# untitled.net
KiCad netlist of a schematic drawn in EAGLE
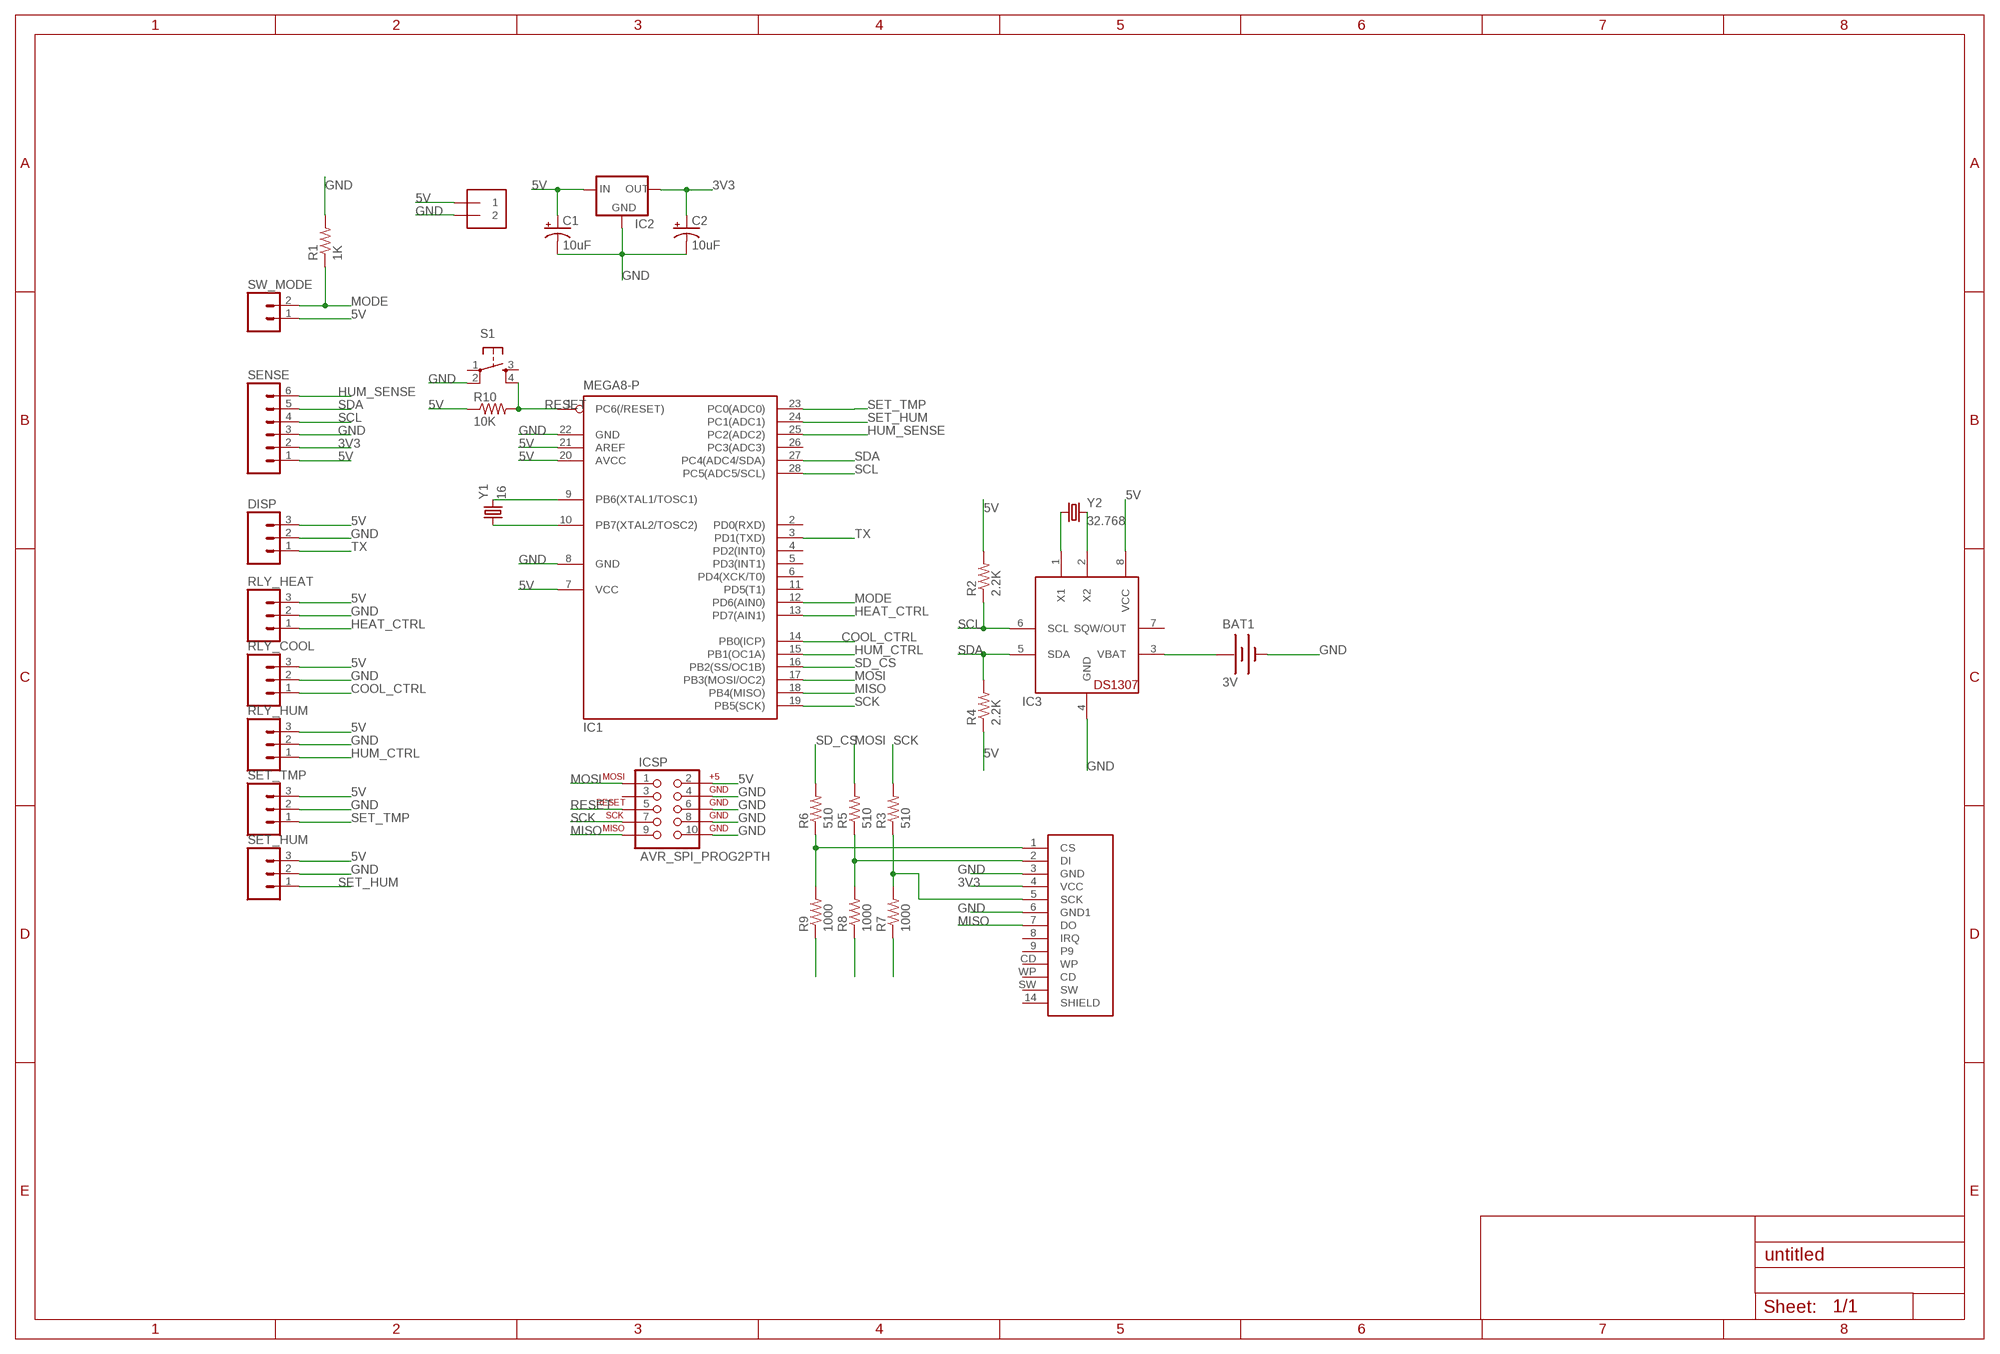
[diagram p0: schematic, sheet 1]

(export (version "E")
  (design (tool "Eeschema 10.0.6"))
  (components
    (comp (ref "BAT1")
      (value "3V")
      (footprint "eagle-import:BATTCOM_20MM_PTH")
      (libsource (lib "eagle-import") (part "BATTERY20PTH"))
    )
    (comp (ref "C1")
      (value "10uF")
      (footprint "eagle-import:CPOL-RADIAL-10UF-25V")
      (libsource (lib "eagle-import") (part "CAP_POLPTH2"))
    )
    (comp (ref "C2")
      (value "10uF")
      (footprint "eagle-import:CPOL-RADIAL-10UF-25V")
      (libsource (lib "eagle-import") (part "CAP_POLPTH2"))
    )
    (comp (ref "DISP")
      (value "M03PTH")
      (footprint "eagle-import:1X03")
      (libsource (lib "eagle-import") (part "M03PTH"))
    )
    (comp (ref "IC1")
      (value "MEGA8-P")
      (footprint "eagle-import:DIL28-3")
      (libsource (lib "eagle-import") (part "MEGA8-P"))
    )
    (comp (ref "IC2")
      (value "V_REG_78XX-TO-220")
      (footprint "eagle-import:TO-220-ALT")
      (libsource (lib "eagle-import") (part "V_REG_78XX-TO-220"))
    )
    (comp (ref "IC3")
      (value "DS1307")
      (footprint "eagle-import:DIL08")
      (libsource (lib "eagle-import") (part "DS1307"))
    )
    (comp (ref "ICSP")
      (value "AVR_SPI_PROG2PTH")
      (footprint "eagle-import:AVR_ICSP")
      (libsource (lib "eagle-import") (part "AVR_SPI_PROG2PTH"))
    )
    (comp (ref "PWR_IN")
      (value "1X2-3.5MM")
      (footprint "eagle-import:1X2-3.5MM")
      (libsource (lib "eagle-import") (part "1X2-3.5MM"))
    )
    (comp (ref "R1")
      (value "1K")
      (footprint "eagle-import:AXIAL-0.3")
      (libsource (lib "eagle-import") (part "SparkFun-Passives_RESISTORAXIAL-0.3"))
    )
    (comp (ref "R2")
      (value "2.2K")
      (footprint "eagle-import:AXIAL-0.3")
      (libsource (lib "eagle-import") (part "SparkFun-Passives_RESISTORAXIAL-0.3"))
    )
    (comp (ref "R3")
      (value "510")
      (footprint "eagle-import:AXIAL-0.3")
      (libsource (lib "eagle-import") (part "SparkFun-Passives_RESISTORAXIAL-0.3"))
    )
    (comp (ref "R4")
      (value "2.2K")
      (footprint "eagle-import:AXIAL-0.3")
      (libsource (lib "eagle-import") (part "SparkFun-Passives_RESISTORAXIAL-0.3"))
    )
    (comp (ref "R5")
      (value "510")
      (footprint "eagle-import:AXIAL-0.3")
      (libsource (lib "eagle-import") (part "SparkFun-Passives_RESISTORAXIAL-0.3"))
    )
    (comp (ref "R6")
      (value "510")
      (footprint "eagle-import:AXIAL-0.3")
      (libsource (lib "eagle-import") (part "SparkFun-Passives_RESISTORAXIAL-0.3"))
    )
    (comp (ref "R7")
      (value "1000")
      (footprint "eagle-import:AXIAL-0.3")
      (libsource (lib "eagle-import") (part "SparkFun-Passives_RESISTORAXIAL-0.3"))
    )
    (comp (ref "R8")
      (value "1000")
      (footprint "eagle-import:AXIAL-0.3")
      (libsource (lib "eagle-import") (part "SparkFun-Passives_RESISTORAXIAL-0.3"))
    )
    (comp (ref "R9")
      (value "1000")
      (footprint "eagle-import:AXIAL-0.3")
      (libsource (lib "eagle-import") (part "SparkFun-Passives_RESISTORAXIAL-0.3"))
    )
    (comp (ref "R10")
      (value "10K")
      (footprint "eagle-import:AXIAL-0.3")
      (libsource (lib "eagle-import") (part "RESISTORAXIAL-0.3"))
    )
    (comp (ref "RLY_COOL")
      (value "M03PTH")
      (footprint "eagle-import:1X03")
      (libsource (lib "eagle-import") (part "M03PTH"))
    )
    (comp (ref "RLY_HEAT")
      (value "M03PTH")
      (footprint "eagle-import:1X03")
      (libsource (lib "eagle-import") (part "M03PTH"))
    )
    (comp (ref "RLY_HUM")
      (value "M03PTH")
      (footprint "eagle-import:1X03")
      (libsource (lib "eagle-import") (part "M03PTH"))
    )
    (comp (ref "S1")
      (value "TAC_SWITCHPTH")
      (footprint "eagle-import:TACTILE-PTH")
      (libsource (lib "eagle-import") (part "TAC_SWITCHPTH"))
    )
    (comp (ref "SD_CARD")
      (value "SD_CARD_SOCKETSD")
      (footprint "eagle-import:SD-MMC_SOCKET-PP")
      (libsource (lib "eagle-import") (part "SD_CARD_SOCKETSD"))
    )
    (comp (ref "SENSE")
      (value "M06SIP")
      (footprint "eagle-import:1X06")
      (libsource (lib "eagle-import") (part "M06SIP"))
    )
    (comp (ref "SET_HUM")
      (value "M03PTH")
      (footprint "eagle-import:1X03")
      (libsource (lib "eagle-import") (part "M03PTH"))
    )
    (comp (ref "SET_TMP")
      (value "M03PTH")
      (footprint "eagle-import:1X03")
      (libsource (lib "eagle-import") (part "M03PTH"))
    )
    (comp (ref "SW_MODE")
      (value "M02JST-PTH-2")
      (footprint "eagle-import:JST-2-PTH")
      (libsource (lib "eagle-import") (part "M02JST-PTH-2"))
    )
    (comp (ref "Y1")
      (value "16")
      (footprint "eagle-import:HC49U-V")
      (libsource (lib "eagle-import") (part "CRYSTALHC49UV"))
    )
    (comp (ref "Y2")
      (value "32.768")
      (footprint "eagle-import:TC26H")
      (libsource (lib "eagle-import") (part "CRYSTALTC26H"))
    )
  )
  (nets
    (net (code "1") (name "/3V3") (class "Default")
      (node (ref "C2") (pin "1") (pinfunction "+_1") (pintype "passive"))
      (node (ref "IC2") (pin "OUT") (pinfunction "OUT_OUT") (pintype "output"))
      (node (ref "SD_CARD") (pin "4") (pinfunction "VCC_4") (pintype "bidirectional"))
      (node (ref "SENSE") (pin "2") (pinfunction "2_2") (pintype "passive"))
    )
    (net (code "2") (name "/5V") (class "Default")
      (node (ref "C1") (pin "1") (pinfunction "+_1") (pintype "passive"))
      (node (ref "DISP") (pin "3") (pinfunction "3_3") (pintype "passive"))
      (node (ref "IC1") (pin "20") (pinfunction "AVCC_20") (pintype "power_in"))
      (node (ref "IC1") (pin "21") (pinfunction "AREF_21") (pintype "passive"))
      (node (ref "IC1") (pin "7") (pinfunction "VCC_7") (pintype "power_in"))
      (node (ref "IC2") (pin "IN") (pinfunction "IN_IN") (pintype "input"))
      (node (ref "IC3") (pin "8") (pinfunction "VCC_8") (pintype "power_in"))
      (node (ref "ICSP") (pin "2") (pinfunction "2_2") (pintype "passive"))
      (node (ref "PWR_IN") (pin "1") (pinfunction "1_1") (pintype "passive"))
      (node (ref "R10") (pin "P$1") (pinfunction "1_P$1") (pintype "passive"))
      (node (ref "R2") (pin "P$2") (pinfunction "2_P$2") (pintype "passive"))
      (node (ref "R4") (pin "P$1") (pinfunction "1_P$1") (pintype "passive"))
      (node (ref "RLY_COOL") (pin "3") (pinfunction "3_3") (pintype "passive"))
      (node (ref "RLY_HEAT") (pin "3") (pinfunction "3_3") (pintype "passive"))
      (node (ref "RLY_HUM") (pin "3") (pinfunction "3_3") (pintype "passive"))
      (node (ref "SENSE") (pin "1") (pinfunction "1_1") (pintype "passive"))
      (node (ref "SET_HUM") (pin "3") (pinfunction "3_3") (pintype "passive"))
      (node (ref "SET_TMP") (pin "3") (pinfunction "3_3") (pintype "passive"))
      (node (ref "SW_MODE") (pin "1") (pinfunction "1_1") (pintype "passive"))
    )
    (net (code "3") (name "/COOL_CTRL") (class "Default")
      (node (ref "IC1") (pin "14") (pinfunction "PB0(ICP)_14") (pintype "bidirectional"))
      (node (ref "RLY_COOL") (pin "1") (pinfunction "1_1") (pintype "passive"))
    )
    (net (code "4") (name "/GND") (class "Default")
      (node (ref "BAT1") (pin "2") (pinfunction "-_2") (pintype "power_in"))
      (node (ref "C1") (pin "2") (pinfunction "-_2") (pintype "passive"))
      (node (ref "C2") (pin "2") (pinfunction "-_2") (pintype "passive"))
      (node (ref "DISP") (pin "2") (pinfunction "2_2") (pintype "passive"))
      (node (ref "IC1") (pin "22") (pinfunction "GND_22") (pintype "power_in"))
      (node (ref "IC1") (pin "8") (pinfunction "GND_8") (pintype "power_in"))
      (node (ref "IC2") (pin "GND") (pinfunction "GND_GND") (pintype "input"))
      (node (ref "IC3") (pin "4") (pinfunction "GND_4") (pintype "power_in"))
      (node (ref "ICSP") (pin "10") (pinfunction "10_10") (pintype "passive"))
      (node (ref "ICSP") (pin "4") (pinfunction "4_4") (pintype "passive"))
      (node (ref "ICSP") (pin "6") (pinfunction "6_6") (pintype "passive"))
      (node (ref "ICSP") (pin "8") (pinfunction "8_8") (pintype "passive"))
      (node (ref "PWR_IN") (pin "2") (pinfunction "2_2") (pintype "passive"))
      (node (ref "R1") (pin "P$2") (pinfunction "2_P$2") (pintype "passive"))
      (node (ref "R7") (pin "P$1") (pinfunction "1_P$1") (pintype "passive"))
      (node (ref "R8") (pin "P$1") (pinfunction "1_P$1") (pintype "passive"))
      (node (ref "R9") (pin "P$1") (pinfunction "1_P$1") (pintype "passive"))
      (node (ref "RLY_COOL") (pin "2") (pinfunction "2_2") (pintype "passive"))
      (node (ref "RLY_HEAT") (pin "2") (pinfunction "2_2") (pintype "passive"))
      (node (ref "RLY_HUM") (pin "2") (pinfunction "2_2") (pintype "passive"))
      (node (ref "S1") (pin "2") (pinfunction "2_2") (pintype "passive"))
      (node (ref "SD_CARD") (pin "3") (pinfunction "GND_3") (pintype "bidirectional"))
      (node (ref "SD_CARD") (pin "6") (pinfunction "GND1_6") (pintype "bidirectional"))
      (node (ref "SENSE") (pin "3") (pinfunction "3_3") (pintype "passive"))
      (node (ref "SET_HUM") (pin "2") (pinfunction "2_2") (pintype "passive"))
      (node (ref "SET_TMP") (pin "2") (pinfunction "2_2") (pintype "passive"))
    )
    (net (code "5") (name "/HEAT_CTRL") (class "Default")
      (node (ref "IC1") (pin "13") (pinfunction "PD7(AIN1)_13") (pintype "bidirectional"))
      (node (ref "RLY_HEAT") (pin "1") (pinfunction "1_1") (pintype "passive"))
    )
    (net (code "6") (name "/HUM_CTRL") (class "Default")
      (node (ref "IC1") (pin "15") (pinfunction "PB1(OC1A)_15") (pintype "bidirectional"))
      (node (ref "RLY_HUM") (pin "1") (pinfunction "1_1") (pintype "passive"))
    )
    (net (code "7") (name "/HUM_SENSE") (class "Default")
      (node (ref "IC1") (pin "25") (pinfunction "PC2(ADC2)_25") (pintype "bidirectional"))
      (node (ref "SENSE") (pin "6") (pinfunction "6_6") (pintype "passive"))
    )
    (net (code "8") (name "/MISO") (class "Default")
      (node (ref "IC1") (pin "18") (pinfunction "PB4(MISO)_18") (pintype "bidirectional"))
      (node (ref "ICSP") (pin "9") (pinfunction "9_9") (pintype "passive"))
      (node (ref "SD_CARD") (pin "7") (pinfunction "DO_7") (pintype "bidirectional"))
    )
    (net (code "9") (name "/MODE") (class "Default")
      (node (ref "IC1") (pin "12") (pinfunction "PD6(AIN0)_12") (pintype "bidirectional"))
      (node (ref "R1") (pin "P$1") (pinfunction "1_P$1") (pintype "passive"))
      (node (ref "SW_MODE") (pin "2") (pinfunction "2_2") (pintype "passive"))
    )
    (net (code "10") (name "/MOSI") (class "Default")
      (node (ref "IC1") (pin "17") (pinfunction "PB3(MOSI/OC2)_17") (pintype "bidirectional"))
      (node (ref "ICSP") (pin "1") (pinfunction "1_1") (pintype "passive"))
      (node (ref "R5") (pin "P$2") (pinfunction "2_P$2") (pintype "passive"))
    )
    (net (code "11") (name "/RESET") (class "Default")
      (node (ref "IC1") (pin "1") (pinfunction "PC6(/RESET)_1") (pintype "bidirectional"))
      (node (ref "ICSP") (pin "5") (pinfunction "5_5") (pintype "passive"))
      (node (ref "R10") (pin "P$2") (pinfunction "2_P$2") (pintype "passive"))
      (node (ref "S1") (pin "4") (pinfunction "4_4") (pintype "passive"))
    )
    (net (code "12") (name "/SCK") (class "Default")
      (node (ref "IC1") (pin "19") (pinfunction "PB5(SCK)_19") (pintype "bidirectional"))
      (node (ref "ICSP") (pin "7") (pinfunction "7_7") (pintype "passive"))
      (node (ref "R3") (pin "P$2") (pinfunction "2_P$2") (pintype "passive"))
    )
    (net (code "13") (name "/SCL") (class "Default")
      (node (ref "IC1") (pin "28") (pinfunction "PC5(ADC5/SCL)_28") (pintype "bidirectional"))
      (node (ref "IC3") (pin "6") (pinfunction "SCL_6") (pintype "bidirectional"))
      (node (ref "R2") (pin "P$1") (pinfunction "1_P$1") (pintype "passive"))
      (node (ref "SENSE") (pin "4") (pinfunction "4_4") (pintype "passive"))
    )
    (net (code "14") (name "/SDA") (class "Default")
      (node (ref "IC1") (pin "27") (pinfunction "PC4(ADC4/SDA)_27") (pintype "bidirectional"))
      (node (ref "IC3") (pin "5") (pinfunction "SDA_5") (pintype "bidirectional"))
      (node (ref "R4") (pin "P$2") (pinfunction "2_P$2") (pintype "passive"))
      (node (ref "SENSE") (pin "5") (pinfunction "5_5") (pintype "passive"))
    )
    (net (code "15") (name "/SD_CS") (class "Default")
      (node (ref "IC1") (pin "16") (pinfunction "PB2(SS/OC1B)_16") (pintype "bidirectional"))
      (node (ref "R6") (pin "P$2") (pinfunction "2_P$2") (pintype "passive"))
    )
    (net (code "16") (name "/SET_HUM") (class "Default")
      (node (ref "IC1") (pin "24") (pinfunction "PC1(ADC1)_24") (pintype "bidirectional"))
      (node (ref "SET_HUM") (pin "1") (pinfunction "1_1") (pintype "passive"))
    )
    (net (code "17") (name "/SET_TMP") (class "Default")
      (node (ref "IC1") (pin "23") (pinfunction "PC0(ADC0)_23") (pintype "bidirectional"))
      (node (ref "SET_TMP") (pin "1") (pinfunction "1_1") (pintype "passive"))
    )
    (net (code "18") (name "/TX") (class "Default")
      (node (ref "DISP") (pin "1") (pinfunction "1_1") (pintype "passive"))
      (node (ref "IC1") (pin "3") (pinfunction "PD1(TXD)_3") (pintype "bidirectional"))
    )
    (net (code "19") (name "Net-(BAT1-+)") (class "Default")
      (node (ref "BAT1") (pin "1") (pinfunction "+_1") (pintype "power_in"))
      (node (ref "IC3") (pin "3") (pinfunction "VBAT_3") (pintype "power_in"))
    )
    (net (code "20") (name "Net-(IC1-PB6(XTAL1{slash}TOSC1))") (class "Default")
      (node (ref "IC1") (pin "9") (pinfunction "PB6(XTAL1/TOSC1)_9") (pintype "bidirectional"))
      (node (ref "Y1") (pin "2") (pinfunction "2_2") (pintype "passive"))
    )
    (net (code "21") (name "Net-(IC1-PB7(XTAL2{slash}TOSC2))") (class "Default")
      (node (ref "IC1") (pin "10") (pinfunction "PB7(XTAL2/TOSC2)_10") (pintype "bidirectional"))
      (node (ref "Y1") (pin "1") (pinfunction "1_1") (pintype "passive"))
    )
    (net (code "22") (name "Net-(IC3-X1)") (class "Default")
      (node (ref "IC3") (pin "1") (pinfunction "X1_1") (pintype "passive"))
      (node (ref "Y2") (pin "1") (pinfunction "1_1") (pintype "passive"))
    )
    (net (code "23") (name "Net-(IC3-X2)") (class "Default")
      (node (ref "IC3") (pin "2") (pinfunction "X2_2") (pintype "passive"))
      (node (ref "Y2") (pin "2") (pinfunction "2_2") (pintype "passive"))
    )
    (net (code "24") (name "Net-(R3-1)") (class "Default")
      (node (ref "R3") (pin "P$1") (pinfunction "1_P$1") (pintype "passive"))
      (node (ref "R7") (pin "P$2") (pinfunction "2_P$2") (pintype "passive"))
      (node (ref "SD_CARD") (pin "5") (pinfunction "SCK_5") (pintype "bidirectional"))
    )
    (net (code "25") (name "Net-(R5-1)") (class "Default")
      (node (ref "R5") (pin "P$1") (pinfunction "1_P$1") (pintype "passive"))
      (node (ref "R8") (pin "P$2") (pinfunction "2_P$2") (pintype "passive"))
      (node (ref "SD_CARD") (pin "2") (pinfunction "DI_2") (pintype "bidirectional"))
    )
    (net (code "26") (name "Net-(R6-1)") (class "Default")
      (node (ref "R6") (pin "P$1") (pinfunction "1_P$1") (pintype "passive"))
      (node (ref "R9") (pin "P$2") (pinfunction "2_P$2") (pintype "passive"))
      (node (ref "SD_CARD") (pin "1") (pinfunction "CS_1") (pintype "bidirectional"))
    )
    (net (code "27") (name "unconnected-(IC1-PC3(ADC3)-Pad26)") (class "Default")
      (node (ref "IC1") (pin "26") (pinfunction "PC3(ADC3)_26") (pintype "bidirectional"))
    )
    (net (code "28") (name "unconnected-(IC1-PD0(RXD)-Pad2)") (class "Default")
      (node (ref "IC1") (pin "2") (pinfunction "PD0(RXD)_2") (pintype "bidirectional"))
    )
    (net (code "29") (name "unconnected-(IC1-PD2(INT0)-Pad4)") (class "Default")
      (node (ref "IC1") (pin "4") (pinfunction "PD2(INT0)_4") (pintype "bidirectional"))
    )
    (net (code "30") (name "unconnected-(IC1-PD3(INT1)-Pad5)") (class "Default")
      (node (ref "IC1") (pin "5") (pinfunction "PD3(INT1)_5") (pintype "bidirectional"))
    )
    (net (code "31") (name "unconnected-(IC1-PD4(XCK{slash}T0)-Pad6)") (class "Default")
      (node (ref "IC1") (pin "6") (pinfunction "PD4(XCK/T0)_6") (pintype "bidirectional"))
    )
    (net (code "32") (name "unconnected-(IC1-PD5(T1)-Pad11)") (class "Default")
      (node (ref "IC1") (pin "11") (pinfunction "PD5(T1)_11") (pintype "bidirectional"))
    )
    (net (code "33") (name "unconnected-(IC3-SQW{slash}OUT-Pad7)") (class "Default")
      (node (ref "IC3") (pin "7") (pinfunction "SQW/OUT_7") (pintype "bidirectional"))
    )
    (net (code "34") (name "unconnected-(ICSP-Pad3)") (class "Default")
      (node (ref "ICSP") (pin "3") (pinfunction "3_3") (pintype "passive"))
    )
    (net (code "35") (name "unconnected-(S1-Pad1)") (class "Default")
      (node (ref "S1") (pin "1") (pinfunction "1_1") (pintype "passive"))
    )
    (net (code "36") (name "unconnected-(S1-Pad3)") (class "Default")
      (node (ref "S1") (pin "3") (pinfunction "3_3") (pintype "passive"))
    )
    (net (code "37") (name "unconnected-(SD_CARD-CD-PadWP)") (class "Default")
      (node (ref "SD_CARD") (pin "WP") (pinfunction "CD_WP") (pintype "bidirectional"))
    )
    (net (code "38") (name "unconnected-(SD_CARD-IRQ-Pad8)") (class "Default")
      (node (ref "SD_CARD") (pin "8") (pinfunction "IRQ_8") (pintype "bidirectional"))
    )
    (net (code "39") (name "unconnected-(SD_CARD-P9-Pad9)") (class "Default")
      (node (ref "SD_CARD") (pin "9") (pinfunction "P9_9") (pintype "bidirectional"))
    )
    (net (code "40") (name "unconnected-(SD_CARD-PadSW)") (class "Default")
      (node (ref "SD_CARD") (pin "SW") (pinfunction "SW_SW") (pintype "bidirectional"))
    )
    (net (code "41") (name "unconnected-(SD_CARD-SHIELD-Pad14)") (class "Default")
      (node (ref "SD_CARD") (pin "14") (pinfunction "SHIELD_14") (pintype "bidirectional"))
    )
    (net (code "42") (name "unconnected-(SD_CARD-WP-PadCD)") (class "Default")
      (node (ref "SD_CARD") (pin "CD") (pinfunction "WP_CD") (pintype "bidirectional"))
    )
  )
)
